# Drivers_-_High_Current.net
KiCad netlist of a schematic drawn in Altium Designer
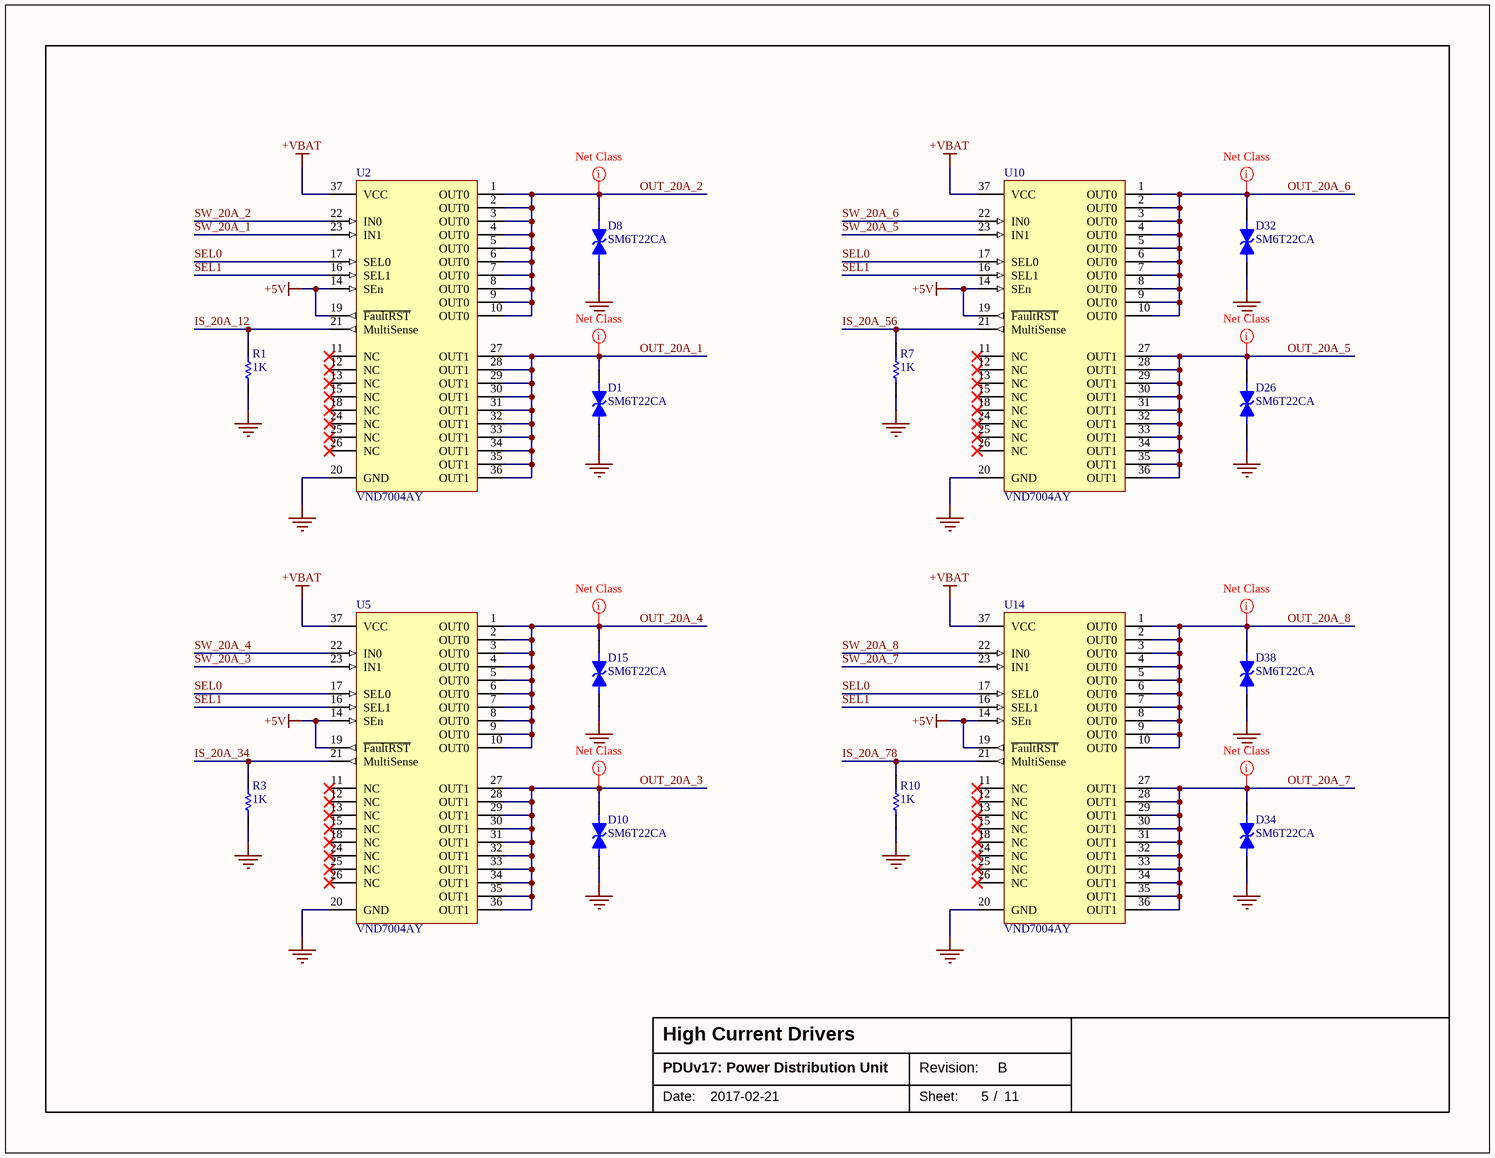
[diagram p0: Drivers - High Current.SchDoc]

(export (version "E")
  (design (tool "Eeschema 10.0.6"))
  (components
    (comp (ref "D1") (value "SM6T22CA") (footprint "SM6T") (libsource (lib "PDU-UV17") (part "SM6T22CA")))
    (comp (ref "D8") (value "SM6T22CA") (footprint "SM6T") (libsource (lib "PDU-UV17") (part "SM6T22CA")))
    (comp (ref "D10") (value "SM6T22CA") (footprint "SM6T") (libsource (lib "PDU-UV17") (part "SM6T22CA")))
    (comp (ref "D15") (value "SM6T22CA") (footprint "SM6T") (libsource (lib "PDU-UV17") (part "SM6T22CA")))
    (comp (ref "D26") (value "SM6T22CA") (footprint "SM6T") (libsource (lib "PDU-UV17") (part "SM6T22CA")))
    (comp (ref "D32") (value "SM6T22CA") (footprint "SM6T") (libsource (lib "PDU-UV17") (part "SM6T22CA")))
    (comp (ref "D34") (value "SM6T22CA") (footprint "SM6T") (libsource (lib "PDU-UV17") (part "SM6T22CA")))
    (comp (ref "D38") (value "SM6T22CA") (footprint "SM6T") (libsource (lib "PDU-UV17") (part "SM6T22CA")))
    (comp (ref "R1")
      (value "1K")
      (footprint "RES-0603-M")
      (fields
        (field (name "PART NUMBER") "RC0603FR-071KL")
        (field (name "TOLERANCE") "1%")
        (field (name "POWER") "1/10 W")
      )
      (libsource (lib "Resistors") (part "Resistor"))
    )
    (comp (ref "R3")
      (value "1K")
      (footprint "RES-0603-M")
      (fields
        (field (name "PART NUMBER") "RC0603FR-071KL")
        (field (name "TOLERANCE") "1%")
        (field (name "POWER") "1/10 W")
      )
      (libsource (lib "Resistors") (part "Resistor"))
    )
    (comp (ref "R7")
      (value "1K")
      (footprint "RES-0603-M")
      (fields
        (field (name "PART NUMBER") "RC0603FR-071KL")
        (field (name "TOLERANCE") "1%")
        (field (name "POWER") "1/10 W")
      )
      (libsource (lib "Resistors") (part "Resistor"))
    )
    (comp (ref "R10")
      (value "1K")
      (footprint "RES-0603-M")
      (fields
        (field (name "PART NUMBER") "RC0603FR-071KL")
        (field (name "TOLERANCE") "1%")
        (field (name "POWER") "1/10 W")
      )
      (libsource (lib "Resistors") (part "Resistor"))
    )
    (comp (ref "U2")
      (value "VND7004AY")
      (footprint "SSOP50P1030X265_HS-37N")
      (libsource (lib "PDU-UV17") (part "VND7004AY"))
    )
    (comp (ref "U5")
      (value "VND7004AY")
      (footprint "SSOP50P1030X265_HS-37N")
      (libsource (lib "PDU-UV17") (part "VND7004AY"))
    )
    (comp (ref "U10")
      (value "VND7004AY")
      (footprint "SSOP50P1030X265_HS-37N")
      (libsource (lib "PDU-UV17") (part "VND7004AY"))
    )
    (comp (ref "U14")
      (value "VND7004AY")
      (footprint "SSOP50P1030X265_HS-37N")
      (libsource (lib "PDU-UV17") (part "VND7004AY"))
    )
  )
  (nets
    (net (code "1") (name "+5V") (class "Default")
      (node (ref "U10") (pin "14") (pinfunction "SEn_14") (pintype "input"))
      (node (ref "U10") (pin "19") (pinfunction "~{FaultRST}_19") (pintype "output"))
      (node (ref "U14") (pin "14") (pinfunction "SEn_14") (pintype "input"))
      (node (ref "U14") (pin "19") (pinfunction "~{FaultRST}_19") (pintype "output"))
      (node (ref "U2") (pin "14") (pinfunction "SEn_14") (pintype "input"))
      (node (ref "U2") (pin "19") (pinfunction "~{FaultRST}_19") (pintype "output"))
      (node (ref "U5") (pin "14") (pinfunction "SEn_14") (pintype "input"))
      (node (ref "U5") (pin "19") (pinfunction "~{FaultRST}_19") (pintype "output"))
    )
    (net (code "2") (name "+VBAT") (class "Default")
      (node (ref "U10") (pin "37") (pinfunction "VCC_37") (pintype "power_in"))
      (node (ref "U14") (pin "37") (pinfunction "VCC_37") (pintype "power_in"))
      (node (ref "U2") (pin "37") (pinfunction "VCC_37") (pintype "power_in"))
      (node (ref "U5") (pin "37") (pinfunction "VCC_37") (pintype "power_in"))
    )
    (net (code "3") (name "/IS_20A_12") (class "Default")
      (node (ref "R1") (pin "2") (pinfunction "2_2") (pintype "passive"))
      (node (ref "U2") (pin "21") (pinfunction "MultiSense_21") (pintype "output"))
    )
    (net (code "4") (name "/IS_20A_34") (class "Default")
      (node (ref "R3") (pin "2") (pinfunction "2_2") (pintype "passive"))
      (node (ref "U5") (pin "21") (pinfunction "MultiSense_21") (pintype "output"))
    )
    (net (code "5") (name "/IS_20A_56") (class "Default")
      (node (ref "R7") (pin "2") (pinfunction "2_2") (pintype "passive"))
      (node (ref "U10") (pin "21") (pinfunction "MultiSense_21") (pintype "output"))
    )
    (net (code "6") (name "/IS_20A_78") (class "Default")
      (node (ref "R10") (pin "2") (pinfunction "2_2") (pintype "passive"))
      (node (ref "U14") (pin "21") (pinfunction "MultiSense_21") (pintype "output"))
    )
    (net (code "7") (name "/OUT_20A_1") (class "Default")
      (node (ref "D1") (pin "2") (pinfunction "A_2") (pintype "passive"))
      (node (ref "U2") (pin "27") (pinfunction "OUT1_27") (pintype "power_in"))
      (node (ref "U2") (pin "28") (pinfunction "OUT1_28") (pintype "power_in"))
      (node (ref "U2") (pin "29") (pinfunction "OUT1_29") (pintype "power_in"))
      (node (ref "U2") (pin "30") (pinfunction "OUT1_30") (pintype "power_in"))
      (node (ref "U2") (pin "31") (pinfunction "OUT1_31") (pintype "power_in"))
      (node (ref "U2") (pin "32") (pinfunction "OUT1_32") (pintype "power_in"))
      (node (ref "U2") (pin "33") (pinfunction "OUT1_33") (pintype "power_in"))
      (node (ref "U2") (pin "34") (pinfunction "OUT1_34") (pintype "power_in"))
      (node (ref "U2") (pin "35") (pinfunction "OUT1_35") (pintype "power_in"))
      (node (ref "U2") (pin "36") (pinfunction "OUT1_36") (pintype "power_in"))
    )
    (net (code "8") (name "/OUT_20A_2") (class "Default")
      (node (ref "D8") (pin "2") (pinfunction "A_2") (pintype "passive"))
      (node (ref "U2") (pin "1") (pinfunction "OUT0_1") (pintype "power_in"))
      (node (ref "U2") (pin "10") (pinfunction "OUT0_10") (pintype "power_in"))
      (node (ref "U2") (pin "2") (pinfunction "OUT0_2") (pintype "power_in"))
      (node (ref "U2") (pin "3") (pinfunction "OUT0_3") (pintype "power_in"))
      (node (ref "U2") (pin "4") (pinfunction "OUT0_4") (pintype "power_in"))
      (node (ref "U2") (pin "5") (pinfunction "OUT0_5") (pintype "power_in"))
      (node (ref "U2") (pin "6") (pinfunction "OUT0_6") (pintype "power_in"))
      (node (ref "U2") (pin "7") (pinfunction "OUT0_7") (pintype "power_in"))
      (node (ref "U2") (pin "8") (pinfunction "OUT0_8") (pintype "power_in"))
      (node (ref "U2") (pin "9") (pinfunction "OUT0_9") (pintype "power_in"))
    )
    (net (code "9") (name "/OUT_20A_3") (class "Default")
      (node (ref "D10") (pin "2") (pinfunction "A_2") (pintype "passive"))
      (node (ref "U5") (pin "27") (pinfunction "OUT1_27") (pintype "power_in"))
      (node (ref "U5") (pin "28") (pinfunction "OUT1_28") (pintype "power_in"))
      (node (ref "U5") (pin "29") (pinfunction "OUT1_29") (pintype "power_in"))
      (node (ref "U5") (pin "30") (pinfunction "OUT1_30") (pintype "power_in"))
      (node (ref "U5") (pin "31") (pinfunction "OUT1_31") (pintype "power_in"))
      (node (ref "U5") (pin "32") (pinfunction "OUT1_32") (pintype "power_in"))
      (node (ref "U5") (pin "33") (pinfunction "OUT1_33") (pintype "power_in"))
      (node (ref "U5") (pin "34") (pinfunction "OUT1_34") (pintype "power_in"))
      (node (ref "U5") (pin "35") (pinfunction "OUT1_35") (pintype "power_in"))
      (node (ref "U5") (pin "36") (pinfunction "OUT1_36") (pintype "power_in"))
    )
    (net (code "10") (name "/OUT_20A_4") (class "Default")
      (node (ref "D15") (pin "2") (pinfunction "A_2") (pintype "passive"))
      (node (ref "U5") (pin "1") (pinfunction "OUT0_1") (pintype "power_in"))
      (node (ref "U5") (pin "10") (pinfunction "OUT0_10") (pintype "power_in"))
      (node (ref "U5") (pin "2") (pinfunction "OUT0_2") (pintype "power_in"))
      (node (ref "U5") (pin "3") (pinfunction "OUT0_3") (pintype "power_in"))
      (node (ref "U5") (pin "4") (pinfunction "OUT0_4") (pintype "power_in"))
      (node (ref "U5") (pin "5") (pinfunction "OUT0_5") (pintype "power_in"))
      (node (ref "U5") (pin "6") (pinfunction "OUT0_6") (pintype "power_in"))
      (node (ref "U5") (pin "7") (pinfunction "OUT0_7") (pintype "power_in"))
      (node (ref "U5") (pin "8") (pinfunction "OUT0_8") (pintype "power_in"))
      (node (ref "U5") (pin "9") (pinfunction "OUT0_9") (pintype "power_in"))
    )
    (net (code "11") (name "/OUT_20A_5") (class "Default")
      (node (ref "D26") (pin "2") (pinfunction "A_2") (pintype "passive"))
      (node (ref "U10") (pin "27") (pinfunction "OUT1_27") (pintype "power_in"))
      (node (ref "U10") (pin "28") (pinfunction "OUT1_28") (pintype "power_in"))
      (node (ref "U10") (pin "29") (pinfunction "OUT1_29") (pintype "power_in"))
      (node (ref "U10") (pin "30") (pinfunction "OUT1_30") (pintype "power_in"))
      (node (ref "U10") (pin "31") (pinfunction "OUT1_31") (pintype "power_in"))
      (node (ref "U10") (pin "32") (pinfunction "OUT1_32") (pintype "power_in"))
      (node (ref "U10") (pin "33") (pinfunction "OUT1_33") (pintype "power_in"))
      (node (ref "U10") (pin "34") (pinfunction "OUT1_34") (pintype "power_in"))
      (node (ref "U10") (pin "35") (pinfunction "OUT1_35") (pintype "power_in"))
      (node (ref "U10") (pin "36") (pinfunction "OUT1_36") (pintype "power_in"))
    )
    (net (code "12") (name "/OUT_20A_6") (class "Default")
      (node (ref "D32") (pin "2") (pinfunction "A_2") (pintype "passive"))
      (node (ref "U10") (pin "1") (pinfunction "OUT0_1") (pintype "power_in"))
      (node (ref "U10") (pin "10") (pinfunction "OUT0_10") (pintype "power_in"))
      (node (ref "U10") (pin "2") (pinfunction "OUT0_2") (pintype "power_in"))
      (node (ref "U10") (pin "3") (pinfunction "OUT0_3") (pintype "power_in"))
      (node (ref "U10") (pin "4") (pinfunction "OUT0_4") (pintype "power_in"))
      (node (ref "U10") (pin "5") (pinfunction "OUT0_5") (pintype "power_in"))
      (node (ref "U10") (pin "6") (pinfunction "OUT0_6") (pintype "power_in"))
      (node (ref "U10") (pin "7") (pinfunction "OUT0_7") (pintype "power_in"))
      (node (ref "U10") (pin "8") (pinfunction "OUT0_8") (pintype "power_in"))
      (node (ref "U10") (pin "9") (pinfunction "OUT0_9") (pintype "power_in"))
    )
    (net (code "13") (name "/OUT_20A_7") (class "Default")
      (node (ref "D34") (pin "2") (pinfunction "A_2") (pintype "passive"))
      (node (ref "U14") (pin "27") (pinfunction "OUT1_27") (pintype "power_in"))
      (node (ref "U14") (pin "28") (pinfunction "OUT1_28") (pintype "power_in"))
      (node (ref "U14") (pin "29") (pinfunction "OUT1_29") (pintype "power_in"))
      (node (ref "U14") (pin "30") (pinfunction "OUT1_30") (pintype "power_in"))
      (node (ref "U14") (pin "31") (pinfunction "OUT1_31") (pintype "power_in"))
      (node (ref "U14") (pin "32") (pinfunction "OUT1_32") (pintype "power_in"))
      (node (ref "U14") (pin "33") (pinfunction "OUT1_33") (pintype "power_in"))
      (node (ref "U14") (pin "34") (pinfunction "OUT1_34") (pintype "power_in"))
      (node (ref "U14") (pin "35") (pinfunction "OUT1_35") (pintype "power_in"))
      (node (ref "U14") (pin "36") (pinfunction "OUT1_36") (pintype "power_in"))
    )
    (net (code "14") (name "/OUT_20A_8") (class "Default")
      (node (ref "D38") (pin "2") (pinfunction "A_2") (pintype "passive"))
      (node (ref "U14") (pin "1") (pinfunction "OUT0_1") (pintype "power_in"))
      (node (ref "U14") (pin "10") (pinfunction "OUT0_10") (pintype "power_in"))
      (node (ref "U14") (pin "2") (pinfunction "OUT0_2") (pintype "power_in"))
      (node (ref "U14") (pin "3") (pinfunction "OUT0_3") (pintype "power_in"))
      (node (ref "U14") (pin "4") (pinfunction "OUT0_4") (pintype "power_in"))
      (node (ref "U14") (pin "5") (pinfunction "OUT0_5") (pintype "power_in"))
      (node (ref "U14") (pin "6") (pinfunction "OUT0_6") (pintype "power_in"))
      (node (ref "U14") (pin "7") (pinfunction "OUT0_7") (pintype "power_in"))
      (node (ref "U14") (pin "8") (pinfunction "OUT0_8") (pintype "power_in"))
      (node (ref "U14") (pin "9") (pinfunction "OUT0_9") (pintype "power_in"))
    )
    (net (code "15") (name "/SEL0") (class "Default")
      (node (ref "U10") (pin "17") (pinfunction "SEL0_17") (pintype "input"))
      (node (ref "U14") (pin "17") (pinfunction "SEL0_17") (pintype "input"))
      (node (ref "U2") (pin "17") (pinfunction "SEL0_17") (pintype "input"))
      (node (ref "U5") (pin "17") (pinfunction "SEL0_17") (pintype "input"))
    )
    (net (code "16") (name "/SEL1") (class "Default")
      (node (ref "U10") (pin "16") (pinfunction "SEL1_16") (pintype "input"))
      (node (ref "U14") (pin "16") (pinfunction "SEL1_16") (pintype "input"))
      (node (ref "U2") (pin "16") (pinfunction "SEL1_16") (pintype "input"))
      (node (ref "U5") (pin "16") (pinfunction "SEL1_16") (pintype "input"))
    )
    (net (code "17") (name "/SW_20A_1") (class "Default")
      (node (ref "U2") (pin "23") (pinfunction "IN1_23") (pintype "input"))
    )
    (net (code "18") (name "/SW_20A_2") (class "Default")
      (node (ref "U2") (pin "22") (pinfunction "IN0_22") (pintype "input"))
    )
    (net (code "19") (name "/SW_20A_3") (class "Default")
      (node (ref "U5") (pin "23") (pinfunction "IN1_23") (pintype "input"))
    )
    (net (code "20") (name "/SW_20A_4") (class "Default")
      (node (ref "U5") (pin "22") (pinfunction "IN0_22") (pintype "input"))
    )
    (net (code "21") (name "/SW_20A_5") (class "Default")
      (node (ref "U10") (pin "23") (pinfunction "IN1_23") (pintype "input"))
    )
    (net (code "22") (name "/SW_20A_6") (class "Default")
      (node (ref "U10") (pin "22") (pinfunction "IN0_22") (pintype "input"))
    )
    (net (code "23") (name "/SW_20A_7") (class "Default")
      (node (ref "U14") (pin "23") (pinfunction "IN1_23") (pintype "input"))
    )
    (net (code "24") (name "/SW_20A_8") (class "Default")
      (node (ref "U14") (pin "22") (pinfunction "IN0_22") (pintype "input"))
    )
    (net (code "25") (name "GND") (class "Default")
      (node (ref "D1") (pin "1") (pinfunction "K_1") (pintype "passive"))
      (node (ref "D10") (pin "1") (pinfunction "K_1") (pintype "passive"))
      (node (ref "D15") (pin "1") (pinfunction "K_1") (pintype "passive"))
      (node (ref "D26") (pin "1") (pinfunction "K_1") (pintype "passive"))
      (node (ref "D32") (pin "1") (pinfunction "K_1") (pintype "passive"))
      (node (ref "D34") (pin "1") (pinfunction "K_1") (pintype "passive"))
      (node (ref "D38") (pin "1") (pinfunction "K_1") (pintype "passive"))
      (node (ref "D8") (pin "1") (pinfunction "K_1") (pintype "passive"))
      (node (ref "R1") (pin "1") (pinfunction "1_1") (pintype "passive"))
      (node (ref "R10") (pin "1") (pinfunction "1_1") (pintype "passive"))
      (node (ref "R3") (pin "1") (pinfunction "1_1") (pintype "passive"))
      (node (ref "R7") (pin "1") (pinfunction "1_1") (pintype "passive"))
      (node (ref "U10") (pin "20") (pinfunction "GND_20") (pintype "power_in"))
      (node (ref "U14") (pin "20") (pinfunction "GND_20") (pintype "power_in"))
      (node (ref "U2") (pin "20") (pinfunction "GND_20") (pintype "power_in"))
      (node (ref "U5") (pin "20") (pinfunction "GND_20") (pintype "power_in"))
    )
    (net (code "26") (name "unconnected-(U2-NC-Pad11)") (class "Default")
      (node (ref "U2") (pin "11") (pinfunction "NC_11") (pintype "passive+no_connect"))
    )
    (net (code "27") (name "unconnected-(U2-NC-Pad12)") (class "Default")
      (node (ref "U2") (pin "12") (pinfunction "NC_12") (pintype "passive+no_connect"))
    )
    (net (code "28") (name "unconnected-(U2-NC-Pad13)") (class "Default")
      (node (ref "U2") (pin "13") (pinfunction "NC_13") (pintype "passive+no_connect"))
    )
    (net (code "29") (name "unconnected-(U2-NC-Pad15)") (class "Default")
      (node (ref "U2") (pin "15") (pinfunction "NC_15") (pintype "passive+no_connect"))
    )
    (net (code "30") (name "unconnected-(U2-NC-Pad18)") (class "Default")
      (node (ref "U2") (pin "18") (pinfunction "NC_18") (pintype "passive+no_connect"))
    )
    (net (code "31") (name "unconnected-(U2-NC-Pad24)") (class "Default")
      (node (ref "U2") (pin "24") (pinfunction "NC_24") (pintype "passive+no_connect"))
    )
    (net (code "32") (name "unconnected-(U2-NC-Pad25)") (class "Default")
      (node (ref "U2") (pin "25") (pinfunction "NC_25") (pintype "passive+no_connect"))
    )
    (net (code "33") (name "unconnected-(U2-NC-Pad26)") (class "Default")
      (node (ref "U2") (pin "26") (pinfunction "NC_26") (pintype "passive+no_connect"))
    )
    (net (code "34") (name "unconnected-(U5-NC-Pad11)") (class "Default")
      (node (ref "U5") (pin "11") (pinfunction "NC_11") (pintype "passive+no_connect"))
    )
    (net (code "35") (name "unconnected-(U5-NC-Pad12)") (class "Default")
      (node (ref "U5") (pin "12") (pinfunction "NC_12") (pintype "passive+no_connect"))
    )
    (net (code "36") (name "unconnected-(U5-NC-Pad13)") (class "Default")
      (node (ref "U5") (pin "13") (pinfunction "NC_13") (pintype "passive+no_connect"))
    )
    (net (code "37") (name "unconnected-(U5-NC-Pad15)") (class "Default")
      (node (ref "U5") (pin "15") (pinfunction "NC_15") (pintype "passive+no_connect"))
    )
    (net (code "38") (name "unconnected-(U5-NC-Pad18)") (class "Default")
      (node (ref "U5") (pin "18") (pinfunction "NC_18") (pintype "passive+no_connect"))
    )
    (net (code "39") (name "unconnected-(U5-NC-Pad24)") (class "Default")
      (node (ref "U5") (pin "24") (pinfunction "NC_24") (pintype "passive+no_connect"))
    )
    (net (code "40") (name "unconnected-(U5-NC-Pad25)") (class "Default")
      (node (ref "U5") (pin "25") (pinfunction "NC_25") (pintype "passive+no_connect"))
    )
    (net (code "41") (name "unconnected-(U5-NC-Pad26)") (class "Default")
      (node (ref "U5") (pin "26") (pinfunction "NC_26") (pintype "passive+no_connect"))
    )
    (net (code "42") (name "unconnected-(U10-NC-Pad11)") (class "Default")
      (node (ref "U10") (pin "11") (pinfunction "NC_11") (pintype "passive+no_connect"))
    )
    (net (code "43") (name "unconnected-(U10-NC-Pad12)") (class "Default")
      (node (ref "U10") (pin "12") (pinfunction "NC_12") (pintype "passive+no_connect"))
    )
    (net (code "44") (name "unconnected-(U10-NC-Pad13)") (class "Default")
      (node (ref "U10") (pin "13") (pinfunction "NC_13") (pintype "passive+no_connect"))
    )
    (net (code "45") (name "unconnected-(U10-NC-Pad15)") (class "Default")
      (node (ref "U10") (pin "15") (pinfunction "NC_15") (pintype "passive+no_connect"))
    )
    (net (code "46") (name "unconnected-(U10-NC-Pad18)") (class "Default")
      (node (ref "U10") (pin "18") (pinfunction "NC_18") (pintype "passive+no_connect"))
    )
    (net (code "47") (name "unconnected-(U10-NC-Pad24)") (class "Default")
      (node (ref "U10") (pin "24") (pinfunction "NC_24") (pintype "passive+no_connect"))
    )
    (net (code "48") (name "unconnected-(U10-NC-Pad25)") (class "Default")
      (node (ref "U10") (pin "25") (pinfunction "NC_25") (pintype "passive+no_connect"))
    )
    (net (code "49") (name "unconnected-(U10-NC-Pad26)") (class "Default")
      (node (ref "U10") (pin "26") (pinfunction "NC_26") (pintype "passive+no_connect"))
    )
    (net (code "50") (name "unconnected-(U14-NC-Pad11)") (class "Default")
      (node (ref "U14") (pin "11") (pinfunction "NC_11") (pintype "passive+no_connect"))
    )
    (net (code "51") (name "unconnected-(U14-NC-Pad12)") (class "Default")
      (node (ref "U14") (pin "12") (pinfunction "NC_12") (pintype "passive+no_connect"))
    )
    (net (code "52") (name "unconnected-(U14-NC-Pad13)") (class "Default")
      (node (ref "U14") (pin "13") (pinfunction "NC_13") (pintype "passive+no_connect"))
    )
    (net (code "53") (name "unconnected-(U14-NC-Pad15)") (class "Default")
      (node (ref "U14") (pin "15") (pinfunction "NC_15") (pintype "passive+no_connect"))
    )
    (net (code "54") (name "unconnected-(U14-NC-Pad18)") (class "Default")
      (node (ref "U14") (pin "18") (pinfunction "NC_18") (pintype "passive+no_connect"))
    )
    (net (code "55") (name "unconnected-(U14-NC-Pad24)") (class "Default")
      (node (ref "U14") (pin "24") (pinfunction "NC_24") (pintype "passive+no_connect"))
    )
    (net (code "56") (name "unconnected-(U14-NC-Pad25)") (class "Default")
      (node (ref "U14") (pin "25") (pinfunction "NC_25") (pintype "passive+no_connect"))
    )
    (net (code "57") (name "unconnected-(U14-NC-Pad26)") (class "Default")
      (node (ref "U14") (pin "26") (pinfunction "NC_26") (pintype "passive+no_connect"))
    )
  )
)
